# FETishOnAStick.net
KiCad netlist of a schematic drawn in EAGLE
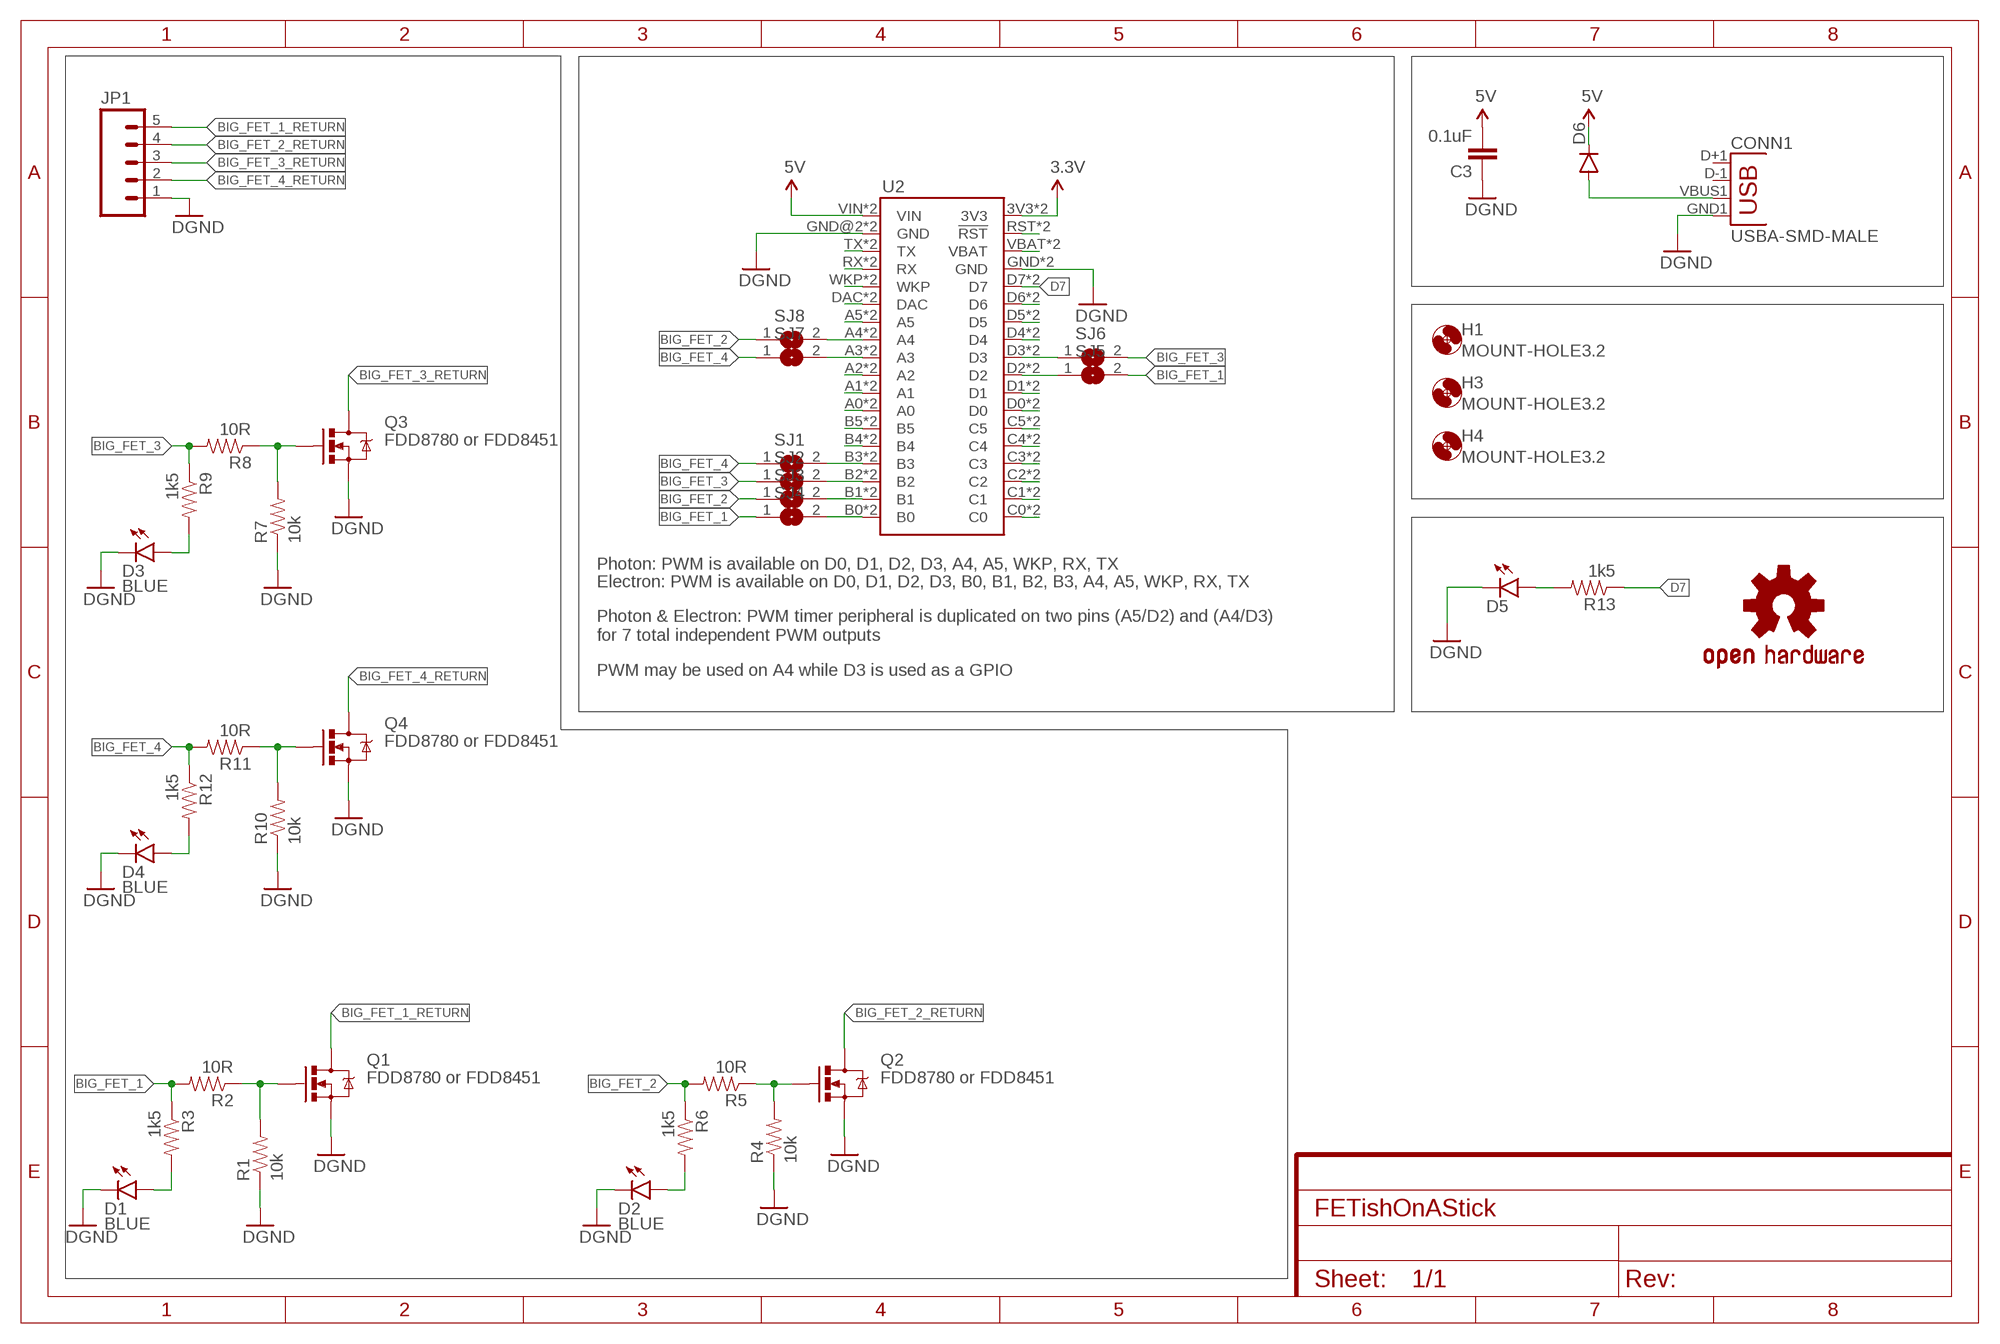
[diagram p0: schematic, sheet 1]

(export (version "E")
  (design (tool "Eeschema 10.0.6"))
  (components
    (comp (ref "C3")
      (value "0.1uF")
      (footprint "eagle-import:0805")
      (libsource (lib "eagle-import") (part "CAP0805"))
    )
    (comp (ref "CONN1")
      (value "USBA-SMD-MALE")
      (footprint "eagle-import:USB-A-SMT-MALE")
      (libsource (lib "eagle-import") (part "USBA-SMD-MALE"))
    )
    (comp (ref "D1")
      (value "BLUE")
      (footprint "eagle-import:LED-1206")
      (libsource (lib "eagle-import") (part "LED-BLUE1206"))
    )
    (comp (ref "D2")
      (value "BLUE")
      (footprint "eagle-import:LED-1206")
      (libsource (lib "eagle-import") (part "LED-BLUE1206"))
    )
    (comp (ref "D3")
      (value "BLUE")
      (footprint "eagle-import:LED-1206")
      (libsource (lib "eagle-import") (part "LED-BLUE1206"))
    )
    (comp (ref "D4")
      (value "BLUE")
      (footprint "eagle-import:LED-1206")
      (libsource (lib "eagle-import") (part "LED-BLUE1206"))
    )
    (comp (ref "D5")
      (value "LED1206-BOTTOM")
      (footprint "eagle-import:LED-1206-BOTTOM")
      (libsource (lib "eagle-import") (part "LED1206-BOTTOM"))
    )
    (comp (ref "D6")
      (value "DIODESMA")
      (footprint "eagle-import:SMA-DIODE")
      (libsource (lib "eagle-import") (part "DIODESMA"))
    )
    (comp (ref "H1")
      (value "MOUNT-HOLE3.2")
      (footprint "eagle-import:3,2")
      (libsource (lib "eagle-import") (part "MOUNT-HOLE3.2"))
    )
    (comp (ref "H3")
      (value "MOUNT-HOLE3.2")
      (footprint "eagle-import:3,2")
      (libsource (lib "eagle-import") (part "MOUNT-HOLE3.2"))
    )
    (comp (ref "H4")
      (value "MOUNT-HOLE3.2")
      (footprint "eagle-import:3,2")
      (libsource (lib "eagle-import") (part "MOUNT-HOLE3.2"))
    )
    (comp (ref "JP1")
      (value "M05SCREW")
      (footprint "eagle-import:SCREWTERMINAL-3.5MM-5")
      (libsource (lib "eagle-import") (part "M05SCREW"))
    )
    (comp (ref "LOGO1")
      (value "OSHW-LOGOM")
      (footprint "eagle-import:OSHW-LOGO-M")
      (libsource (lib "eagle-import") (part "OSHW-LOGOM"))
    )
    (comp (ref "Q1")
      (value "FDD8780 or FDD8451")
      (footprint "eagle-import:DPAK")
      (libsource (lib "eagle-import") (part "MOSFET-NCHANNELFDD8780"))
    )
    (comp (ref "Q2")
      (value "FDD8780 or FDD8451")
      (footprint "eagle-import:DPAK")
      (libsource (lib "eagle-import") (part "MOSFET-NCHANNELFDD8780"))
    )
    (comp (ref "Q3")
      (value "FDD8780 or FDD8451")
      (footprint "eagle-import:DPAK")
      (libsource (lib "eagle-import") (part "MOSFET-NCHANNELFDD8780"))
    )
    (comp (ref "Q4")
      (value "FDD8780 or FDD8451")
      (footprint "eagle-import:DPAK")
      (libsource (lib "eagle-import") (part "MOSFET-NCHANNELFDD8780"))
    )
    (comp (ref "R1")
      (value "10k")
      (footprint "eagle-import:0805")
      (libsource (lib "eagle-import") (part "RESISTOR0805-RES"))
    )
    (comp (ref "R2")
      (value "10R")
      (footprint "eagle-import:0805")
      (libsource (lib "eagle-import") (part "RESISTOR0805-RES"))
    )
    (comp (ref "R3")
      (value "1k5")
      (footprint "eagle-import:0805")
      (libsource (lib "eagle-import") (part "RESISTOR0805-RES"))
    )
    (comp (ref "R4")
      (value "10k")
      (footprint "eagle-import:0805")
      (libsource (lib "eagle-import") (part "RESISTOR0805-RES"))
    )
    (comp (ref "R5")
      (value "10R")
      (footprint "eagle-import:0805")
      (libsource (lib "eagle-import") (part "RESISTOR0805-RES"))
    )
    (comp (ref "R6")
      (value "1k5")
      (footprint "eagle-import:0805")
      (libsource (lib "eagle-import") (part "RESISTOR0805-RES"))
    )
    (comp (ref "R7")
      (value "10k")
      (footprint "eagle-import:0805")
      (libsource (lib "eagle-import") (part "RESISTOR0805-RES"))
    )
    (comp (ref "R8")
      (value "10R")
      (footprint "eagle-import:0805")
      (libsource (lib "eagle-import") (part "RESISTOR0805-RES"))
    )
    (comp (ref "R9")
      (value "1k5")
      (footprint "eagle-import:0805")
      (libsource (lib "eagle-import") (part "RESISTOR0805-RES"))
    )
    (comp (ref "R10")
      (value "10k")
      (footprint "eagle-import:0805")
      (libsource (lib "eagle-import") (part "RESISTOR0805-RES"))
    )
    (comp (ref "R11")
      (value "10R")
      (footprint "eagle-import:0805")
      (libsource (lib "eagle-import") (part "RESISTOR0805-RES"))
    )
    (comp (ref "R12")
      (value "1k5")
      (footprint "eagle-import:0805")
      (libsource (lib "eagle-import") (part "RESISTOR0805-RES"))
    )
    (comp (ref "R13")
      (value "1k5")
      (footprint "eagle-import:0805")
      (libsource (lib "eagle-import") (part "RESISTOR0805-RES"))
    )
    (comp (ref "SJ1") (value "SJ") (footprint "eagle-import:SJ") (libsource (lib "eagle-import") (part "SJ")))
    (comp (ref "SJ2") (value "SJ") (footprint "eagle-import:SJ") (libsource (lib "eagle-import") (part "SJ")))
    (comp (ref "SJ3") (value "SJ") (footprint "eagle-import:SJ") (libsource (lib "eagle-import") (part "SJ")))
    (comp (ref "SJ4") (value "SJ") (footprint "eagle-import:SJ") (libsource (lib "eagle-import") (part "SJ")))
    (comp (ref "SJ5") (value "SJ") (footprint "eagle-import:SJ") (libsource (lib "eagle-import") (part "SJ")))
    (comp (ref "SJ6") (value "SJ") (footprint "eagle-import:SJ") (libsource (lib "eagle-import") (part "SJ")))
    (comp (ref "SJ7") (value "SJ") (footprint "eagle-import:SJ") (libsource (lib "eagle-import") (part "SJ")))
    (comp (ref "SJ8") (value "SJ") (footprint "eagle-import:SJ") (libsource (lib "eagle-import") (part "SJ")))
    (comp (ref "U2")
      (value "ELECTRONDUALNAMED")
      (footprint "eagle-import:ELECTRON_SIMPLE_SILK_NAMES_DUAL")
      (libsource (lib "eagle-import") (part "ELECTRONDUALNAMED"))
    )
  )
  (nets
    (net (code "1") (name "3.3V") (class "Default")
      (node (ref "U2") (pin "3V3") (pinfunction "3V3_3V3") (pintype "power_in"))
      (node (ref "U2") (pin "3V3_1") (pinfunction "3V3_3V3_1") (pintype "power_in"))
    )
    (net (code "2") (name "5V") (class "Default")
      (node (ref "C3") (pin "2") (pinfunction "2_2") (pintype "passive"))
      (node (ref "D6") (pin "C") (pinfunction "C_C") (pintype "passive"))
      (node (ref "U2") (pin "VIN") (pinfunction "VIN_VIN") (pintype "power_in"))
      (node (ref "U2") (pin "VIN_1B") (pinfunction "VIN_VIN_1B") (pintype "power_in"))
    )
    (net (code "3") (name "BIG_FET_1") (class "Default")
      (node (ref "R2") (pin "2") (pinfunction "2_2") (pintype "passive"))
      (node (ref "R3") (pin "1") (pinfunction "1_1") (pintype "passive"))
      (node (ref "SJ4") (pin "1") (pinfunction "1_1") (pintype "passive"))
      (node (ref "SJ5") (pin "2") (pinfunction "2_2") (pintype "passive"))
    )
    (net (code "4") (name "BIG_FET_1_RETURN") (class "Default")
      (node (ref "JP1") (pin "5") (pinfunction "5_5") (pintype "passive"))
      (node (ref "Q1") (pin "4") (pinfunction "D_4") (pintype "passive"))
    )
    (net (code "5") (name "BIG_FET_2") (class "Default")
      (node (ref "R5") (pin "2") (pinfunction "2_2") (pintype "passive"))
      (node (ref "R6") (pin "1") (pinfunction "1_1") (pintype "passive"))
      (node (ref "SJ3") (pin "1") (pinfunction "1_1") (pintype "passive"))
      (node (ref "SJ8") (pin "1") (pinfunction "1_1") (pintype "passive"))
    )
    (net (code "6") (name "BIG_FET_2_RETURN") (class "Default")
      (node (ref "JP1") (pin "4") (pinfunction "4_4") (pintype "passive"))
      (node (ref "Q2") (pin "4") (pinfunction "D_4") (pintype "passive"))
    )
    (net (code "7") (name "BIG_FET_3") (class "Default")
      (node (ref "R8") (pin "2") (pinfunction "2_2") (pintype "passive"))
      (node (ref "R9") (pin "1") (pinfunction "1_1") (pintype "passive"))
      (node (ref "SJ2") (pin "1") (pinfunction "1_1") (pintype "passive"))
      (node (ref "SJ6") (pin "2") (pinfunction "2_2") (pintype "passive"))
    )
    (net (code "8") (name "BIG_FET_3_RETURN") (class "Default")
      (node (ref "JP1") (pin "3") (pinfunction "3_3") (pintype "passive"))
      (node (ref "Q3") (pin "4") (pinfunction "D_4") (pintype "passive"))
    )
    (net (code "9") (name "BIG_FET_4") (class "Default")
      (node (ref "R11") (pin "2") (pinfunction "2_2") (pintype "passive"))
      (node (ref "R12") (pin "1") (pinfunction "1_1") (pintype "passive"))
      (node (ref "SJ1") (pin "1") (pinfunction "1_1") (pintype "passive"))
      (node (ref "SJ7") (pin "1") (pinfunction "1_1") (pintype "passive"))
    )
    (net (code "10") (name "BIG_FET_4_RETURN") (class "Default")
      (node (ref "JP1") (pin "2") (pinfunction "2_2") (pintype "passive"))
      (node (ref "Q4") (pin "4") (pinfunction "D_4") (pintype "passive"))
    )
    (net (code "11") (name "D7") (class "Default")
      (node (ref "R13") (pin "1") (pinfunction "1_1") (pintype "passive"))
      (node (ref "U2") (pin "D7") (pinfunction "D7_D7") (pintype "bidirectional"))
      (node (ref "U2") (pin "D7_1") (pinfunction "D7_D7_1") (pintype "bidirectional"))
    )
    (net (code "12") (name "DGND") (class "Default")
      (node (ref "C3") (pin "1") (pinfunction "1_1") (pintype "passive"))
      (node (ref "CONN1") (pin "GND1") (pinfunction "GND_GND1") (pintype "bidirectional"))
      (node (ref "D1") (pin "C") (pinfunction "C_C") (pintype "passive"))
      (node (ref "D2") (pin "C") (pinfunction "C_C") (pintype "passive"))
      (node (ref "D3") (pin "C") (pinfunction "C_C") (pintype "passive"))
      (node (ref "D4") (pin "C") (pinfunction "C_C") (pintype "passive"))
      (node (ref "D5") (pin "C") (pinfunction "C_C") (pintype "passive"))
      (node (ref "JP1") (pin "1") (pinfunction "1_1") (pintype "passive"))
      (node (ref "Q1") (pin "3") (pinfunction "S_3") (pintype "passive"))
      (node (ref "Q2") (pin "3") (pinfunction "S_3") (pintype "passive"))
      (node (ref "Q3") (pin "3") (pinfunction "S_3") (pintype "passive"))
      (node (ref "Q4") (pin "3") (pinfunction "S_3") (pintype "passive"))
      (node (ref "R1") (pin "1") (pinfunction "1_1") (pintype "passive"))
      (node (ref "R10") (pin "1") (pinfunction "1_1") (pintype "passive"))
      (node (ref "R4") (pin "1") (pinfunction "1_1") (pintype "passive"))
      (node (ref "R7") (pin "1") (pinfunction "1_1") (pintype "passive"))
      (node (ref "U2") (pin "GND") (pinfunction "GND_GND") (pintype "power_in"))
      (node (ref "U2") (pin "GND@2") (pinfunction "GND_GND@2") (pintype "power_in"))
      (node (ref "U2") (pin "GND_1") (pinfunction "GND_GND_1") (pintype "power_in"))
      (node (ref "U2") (pin "GND_1B") (pinfunction "GND_GND_1B") (pintype "power_in"))
    )
    (net (code "13") (name "Net-(CONN1-VBUS)") (class "Default")
      (node (ref "CONN1") (pin "VBUS1") (pinfunction "VBUS_VBUS1") (pintype "bidirectional"))
      (node (ref "D6") (pin "A") (pinfunction "A_A") (pintype "passive"))
    )
    (net (code "14") (name "Net-(D1-PadA)") (class "Default")
      (node (ref "D1") (pin "A") (pinfunction "A_A") (pintype "passive"))
      (node (ref "R3") (pin "2") (pinfunction "2_2") (pintype "passive"))
    )
    (net (code "15") (name "Net-(D2-PadA)") (class "Default")
      (node (ref "D2") (pin "A") (pinfunction "A_A") (pintype "passive"))
      (node (ref "R6") (pin "2") (pinfunction "2_2") (pintype "passive"))
    )
    (net (code "16") (name "Net-(D3-PadA)") (class "Default")
      (node (ref "D3") (pin "A") (pinfunction "A_A") (pintype "passive"))
      (node (ref "R9") (pin "2") (pinfunction "2_2") (pintype "passive"))
    )
    (net (code "17") (name "Net-(D4-PadA)") (class "Default")
      (node (ref "D4") (pin "A") (pinfunction "A_A") (pintype "passive"))
      (node (ref "R12") (pin "2") (pinfunction "2_2") (pintype "passive"))
    )
    (net (code "18") (name "Net-(D5-PadA)") (class "Default")
      (node (ref "D5") (pin "A") (pinfunction "A_A") (pintype "passive"))
      (node (ref "R13") (pin "2") (pinfunction "2_2") (pintype "passive"))
    )
    (net (code "19") (name "Net-(Q1-G)") (class "Default")
      (node (ref "Q1") (pin "1") (pinfunction "G_1") (pintype "passive"))
      (node (ref "R1") (pin "2") (pinfunction "2_2") (pintype "passive"))
      (node (ref "R2") (pin "1") (pinfunction "1_1") (pintype "passive"))
    )
    (net (code "20") (name "Net-(Q2-G)") (class "Default")
      (node (ref "Q2") (pin "1") (pinfunction "G_1") (pintype "passive"))
      (node (ref "R4") (pin "2") (pinfunction "2_2") (pintype "passive"))
      (node (ref "R5") (pin "1") (pinfunction "1_1") (pintype "passive"))
    )
    (net (code "21") (name "Net-(Q3-G)") (class "Default")
      (node (ref "Q3") (pin "1") (pinfunction "G_1") (pintype "passive"))
      (node (ref "R7") (pin "2") (pinfunction "2_2") (pintype "passive"))
      (node (ref "R8") (pin "1") (pinfunction "1_1") (pintype "passive"))
    )
    (net (code "22") (name "Net-(Q4-G)") (class "Default")
      (node (ref "Q4") (pin "1") (pinfunction "G_1") (pintype "passive"))
      (node (ref "R10") (pin "2") (pinfunction "2_2") (pintype "passive"))
      (node (ref "R11") (pin "1") (pinfunction "1_1") (pintype "passive"))
    )
    (net (code "23") (name "Net-(SJ1-Pad2)") (class "Default")
      (node (ref "SJ1") (pin "2") (pinfunction "2_2") (pintype "passive"))
      (node (ref "U2") (pin "B3") (pinfunction "B3_B3") (pintype "bidirectional"))
      (node (ref "U2") (pin "B3_1") (pinfunction "B3_B3_1") (pintype "bidirectional"))
    )
    (net (code "24") (name "Net-(SJ2-Pad2)") (class "Default")
      (node (ref "SJ2") (pin "2") (pinfunction "2_2") (pintype "passive"))
      (node (ref "U2") (pin "B2") (pinfunction "B2_B2") (pintype "bidirectional"))
      (node (ref "U2") (pin "B2_1") (pinfunction "B2_B2_1") (pintype "bidirectional"))
    )
    (net (code "25") (name "Net-(SJ3-Pad2)") (class "Default")
      (node (ref "SJ3") (pin "2") (pinfunction "2_2") (pintype "passive"))
      (node (ref "U2") (pin "B1") (pinfunction "B1_B1") (pintype "bidirectional"))
      (node (ref "U2") (pin "B1_1") (pinfunction "B1_B1_1") (pintype "bidirectional"))
    )
    (net (code "26") (name "Net-(SJ4-Pad2)") (class "Default")
      (node (ref "SJ4") (pin "2") (pinfunction "2_2") (pintype "passive"))
      (node (ref "U2") (pin "B0") (pinfunction "B0_B0") (pintype "bidirectional"))
      (node (ref "U2") (pin "B0_1") (pinfunction "B0_B0_1") (pintype "bidirectional"))
    )
    (net (code "27") (name "Net-(SJ5-Pad1)") (class "Default")
      (node (ref "SJ5") (pin "1") (pinfunction "1_1") (pintype "passive"))
      (node (ref "U2") (pin "D2") (pinfunction "D2_D2") (pintype "bidirectional"))
      (node (ref "U2") (pin "D2_1") (pinfunction "D2_D2_1") (pintype "bidirectional"))
    )
    (net (code "28") (name "Net-(SJ6-Pad1)") (class "Default")
      (node (ref "SJ6") (pin "1") (pinfunction "1_1") (pintype "passive"))
      (node (ref "U2") (pin "D3") (pinfunction "D3_D3") (pintype "bidirectional"))
      (node (ref "U2") (pin "D3_1") (pinfunction "D3_D3_1") (pintype "bidirectional"))
    )
    (net (code "29") (name "Net-(SJ7-Pad2)") (class "Default")
      (node (ref "SJ7") (pin "2") (pinfunction "2_2") (pintype "passive"))
      (node (ref "U2") (pin "A3") (pinfunction "A3_A3") (pintype "bidirectional"))
      (node (ref "U2") (pin "A3_1") (pinfunction "A3_A3_1") (pintype "bidirectional"))
    )
    (net (code "30") (name "Net-(SJ8-Pad2)") (class "Default")
      (node (ref "SJ8") (pin "2") (pinfunction "2_2") (pintype "passive"))
      (node (ref "U2") (pin "A4") (pinfunction "A4_A4") (pintype "bidirectional"))
      (node (ref "U2") (pin "A4_1") (pinfunction "A4_A4_1") (pintype "bidirectional"))
    )
    (net (code "31") (name "Net-(U2-A0-PadA0_1)") (class "Default")
      (node (ref "U2") (pin "A0") (pinfunction "A0_A0") (pintype "bidirectional"))
      (node (ref "U2") (pin "A0_1") (pinfunction "A0_A0_1") (pintype "bidirectional"))
    )
    (net (code "32") (name "Net-(U2-A1-PadA1_1)") (class "Default")
      (node (ref "U2") (pin "A1") (pinfunction "A1_A1") (pintype "bidirectional"))
      (node (ref "U2") (pin "A1_1") (pinfunction "A1_A1_1") (pintype "bidirectional"))
    )
    (net (code "33") (name "Net-(U2-A2-PadA2_1)") (class "Default")
      (node (ref "U2") (pin "A2") (pinfunction "A2_A2") (pintype "bidirectional"))
      (node (ref "U2") (pin "A2_1") (pinfunction "A2_A2_1") (pintype "bidirectional"))
    )
    (net (code "34") (name "Net-(U2-A5-PadA5_1)") (class "Default")
      (node (ref "U2") (pin "A5") (pinfunction "A5_A5") (pintype "bidirectional"))
      (node (ref "U2") (pin "A5_1") (pinfunction "A5_A5_1") (pintype "bidirectional"))
    )
    (net (code "35") (name "Net-(U2-B4-PadB4_1)") (class "Default")
      (node (ref "U2") (pin "B4") (pinfunction "B4_B4") (pintype "bidirectional"))
      (node (ref "U2") (pin "B4_1") (pinfunction "B4_B4_1") (pintype "bidirectional"))
    )
    (net (code "36") (name "Net-(U2-B5-PadB5_1)") (class "Default")
      (node (ref "U2") (pin "B5") (pinfunction "B5_B5") (pintype "bidirectional"))
      (node (ref "U2") (pin "B5_1") (pinfunction "B5_B5_1") (pintype "bidirectional"))
    )
    (net (code "37") (name "Net-(U2-C0-PadC0_1)") (class "Default")
      (node (ref "U2") (pin "C0") (pinfunction "C0_C0") (pintype "bidirectional"))
      (node (ref "U2") (pin "C0_1") (pinfunction "C0_C0_1") (pintype "bidirectional"))
    )
    (net (code "38") (name "Net-(U2-C1-PadC1_1)") (class "Default")
      (node (ref "U2") (pin "C1") (pinfunction "C1_C1") (pintype "bidirectional"))
      (node (ref "U2") (pin "C1_1") (pinfunction "C1_C1_1") (pintype "bidirectional"))
    )
    (net (code "39") (name "Net-(U2-C2-PadC2_1)") (class "Default")
      (node (ref "U2") (pin "C2") (pinfunction "C2_C2") (pintype "bidirectional"))
      (node (ref "U2") (pin "C2_1") (pinfunction "C2_C2_1") (pintype "bidirectional"))
    )
    (net (code "40") (name "Net-(U2-C3-PadC3_1)") (class "Default")
      (node (ref "U2") (pin "C3") (pinfunction "C3_C3") (pintype "bidirectional"))
      (node (ref "U2") (pin "C3_1") (pinfunction "C3_C3_1") (pintype "bidirectional"))
    )
    (net (code "41") (name "Net-(U2-C4-PadC4_1)") (class "Default")
      (node (ref "U2") (pin "C4") (pinfunction "C4_C4") (pintype "bidirectional"))
      (node (ref "U2") (pin "C4_1") (pinfunction "C4_C4_1") (pintype "bidirectional"))
    )
    (net (code "42") (name "Net-(U2-C5-PadC5_1)") (class "Default")
      (node (ref "U2") (pin "C5") (pinfunction "C5_C5") (pintype "bidirectional"))
      (node (ref "U2") (pin "C5_1") (pinfunction "C5_C5_1") (pintype "bidirectional"))
    )
    (net (code "43") (name "Net-(U2-D0-PadD0_1)") (class "Default")
      (node (ref "U2") (pin "D0") (pinfunction "D0_D0") (pintype "bidirectional"))
      (node (ref "U2") (pin "D0_1") (pinfunction "D0_D0_1") (pintype "bidirectional"))
    )
    (net (code "44") (name "Net-(U2-D1-PadD1_1)") (class "Default")
      (node (ref "U2") (pin "D1") (pinfunction "D1_D1") (pintype "bidirectional"))
      (node (ref "U2") (pin "D1_1") (pinfunction "D1_D1_1") (pintype "bidirectional"))
    )
    (net (code "45") (name "Net-(U2-D4-PadD4_1)") (class "Default")
      (node (ref "U2") (pin "D4") (pinfunction "D4_D4") (pintype "bidirectional"))
      (node (ref "U2") (pin "D4_1") (pinfunction "D4_D4_1") (pintype "bidirectional"))
    )
    (net (code "46") (name "Net-(U2-D5-PadD5_1)") (class "Default")
      (node (ref "U2") (pin "D5") (pinfunction "D5_D5") (pintype "bidirectional"))
      (node (ref "U2") (pin "D5_1") (pinfunction "D5_D5_1") (pintype "bidirectional"))
    )
    (net (code "47") (name "Net-(U2-D6-PadD6_1)") (class "Default")
      (node (ref "U2") (pin "D6") (pinfunction "D6_D6") (pintype "bidirectional"))
      (node (ref "U2") (pin "D6_1") (pinfunction "D6_D6_1") (pintype "bidirectional"))
    )
    (net (code "48") (name "Net-(U2-DAC-PadDAC_1)") (class "Default")
      (node (ref "U2") (pin "DAC") (pinfunction "DAC_DAC") (pintype "bidirectional"))
      (node (ref "U2") (pin "DAC_1") (pinfunction "DAC_DAC_1") (pintype "bidirectional"))
    )
    (net (code "49") (name "Net-(U2-PadRX)") (class "Default")
      (node (ref "U2") (pin "RX") (pinfunction "RX_RX") (pintype "bidirectional"))
      (node (ref "U2") (pin "RX_1") (pinfunction "RX_RX_1") (pintype "bidirectional"))
    )
    (net (code "50") (name "Net-(U2-PadTX)") (class "Default")
      (node (ref "U2") (pin "TX") (pinfunction "TX_TX") (pintype "bidirectional"))
      (node (ref "U2") (pin "TX_1") (pinfunction "TX_TX_1") (pintype "bidirectional"))
    )
    (net (code "51") (name "Net-(U2-PadVBAT)") (class "Default")
      (node (ref "U2") (pin "VBAT") (pinfunction "VBAT_VBAT") (pintype "passive"))
      (node (ref "U2") (pin "VBATT_1") (pinfunction "VBAT_VBATT_1") (pintype "passive"))
    )
    (net (code "52") (name "Net-(U2-PadWKP)") (class "Default")
      (node (ref "U2") (pin "WKP") (pinfunction "WKP_WKP") (pintype "bidirectional"))
      (node (ref "U2") (pin "WKP_1") (pinfunction "WKP_WKP_1") (pintype "bidirectional"))
    )
    (net (code "53") (name "Net-(U2-~{RST}-PadRST)") (class "Default")
      (node (ref "U2") (pin "RST") (pinfunction "~{RST}_RST") (pintype "bidirectional"))
      (node (ref "U2") (pin "RST_1") (pinfunction "~{RST}_RST_1") (pintype "bidirectional"))
    )
    (net (code "54") (name "unconnected-(CONN1-D+-PadD+1)") (class "Default")
      (node (ref "CONN1") (pin "D+1") (pinfunction "D+_D+1") (pintype "bidirectional"))
    )
    (net (code "55") (name "unconnected-(CONN1-D--PadD-1)") (class "Default")
      (node (ref "CONN1") (pin "D-1") (pinfunction "D-_D-1") (pintype "bidirectional"))
    )
  )
)
